# DoomBoxMk1.net
KiCad netlist of a schematic drawn in EAGLE
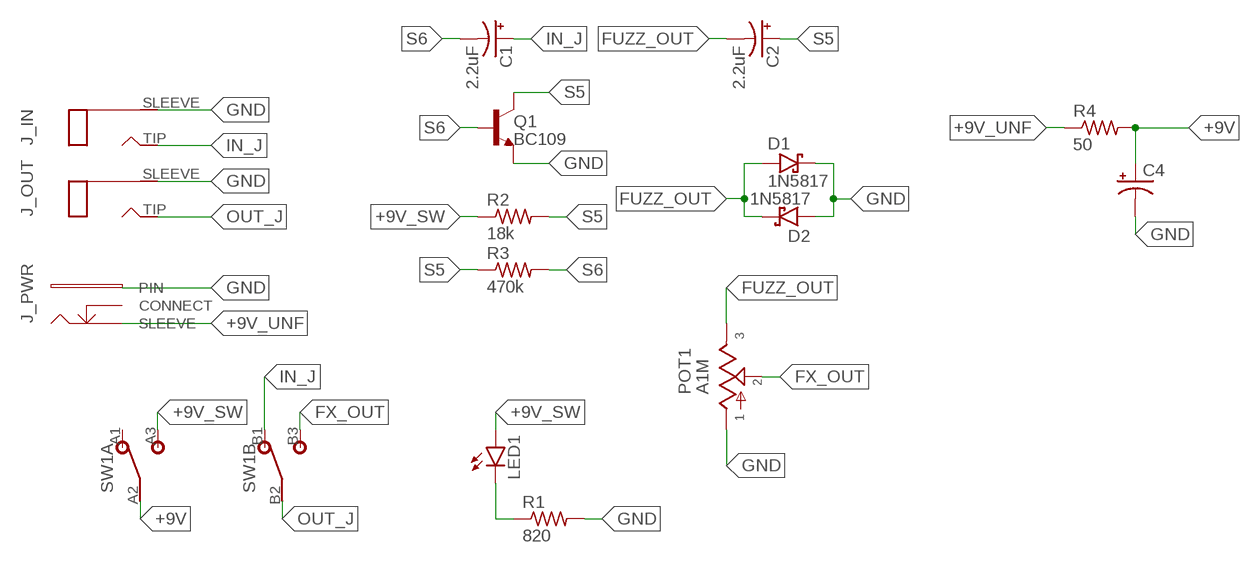
[diagram p0: schematic, sheet 1]

(export (version "E")
  (design (tool "Eeschema 10.0.6"))
  (components
    (comp (ref "C1")
      (value "2.2uF")
      (footprint "eagle-import:050_020_1")
      (libsource (lib "eagle-import") (part "0501"))
    )
    (comp (ref "C2")
      (value "2.2uF")
      (footprint "eagle-import:050_020_1")
      (libsource (lib "eagle-import") (part "0501"))
    )
    (comp (ref "C4")
      (value "0802")
      (footprint "eagle-import:080_035_2")
      (libsource (lib "eagle-import") (part "0802"))
    )
    (comp (ref "D1")
      (value "1N5817")
      (footprint "eagle-import:DO41-3")
      (libsource (lib "eagle-import") (part "1N5817"))
    )
    (comp (ref "D2")
      (value "1N5817")
      (footprint "eagle-import:DO41-3")
      (libsource (lib "eagle-import") (part "1N5817"))
    )
    (comp (ref "J_IN")
      (value "MONO")
      (footprint "eagle-import:MONO_JACK")
      (libsource (lib "eagle-import") (part "MONO"))
    )
    (comp (ref "J_OUT")
      (value "MONO")
      (footprint "eagle-import:MONO_JACK")
      (libsource (lib "eagle-import") (part "MONO"))
    )
    (comp (ref "J_PWR")
      (value "DC")
      (footprint "eagle-import:DC_POWER_JACK")
      (libsource (lib "eagle-import") (part "DC"))
    )
    (comp (ref "LED1")
      (value "LED5MM")
      (footprint "eagle-import:LED5MM")
      (libsource (lib "eagle-import") (part "LED5MM"))
    )
    (comp (ref "POT1")
      (value "A1M")
      (footprint "eagle-import:16MM-SQUARE")
      (libsource (lib "eagle-import") (part "POTS"))
    )
    (comp (ref "Q1")
      (value "BC109")
      (footprint "eagle-import:TO92-")
      (libsource (lib "eagle-import") (part "BC109"))
    )
    (comp (ref "R1")
      (value "820")
      (footprint "eagle-import:R0207_3")
      (libsource (lib "eagle-import") (part "6MM.3"))
    )
    (comp (ref "R2")
      (value "18k")
      (footprint "eagle-import:R0207_3")
      (libsource (lib "eagle-import") (part "6MM.3"))
    )
    (comp (ref "R3")
      (value "470k")
      (footprint "eagle-import:R0207_3")
      (libsource (lib "eagle-import") (part "6MM.3"))
    )
    (comp (ref "R4")
      (value "50")
      (footprint "eagle-import:R0207_3")
      (libsource (lib "eagle-import") (part "6MM.3"))
    )
    (comp (ref "SW1")
      (value "DPDT")
      (footprint "eagle-import:DPDT")
      (libsource (lib "eagle-import") (part "DPDT"))
    )
  )
  (nets
    (net (code "1") (name "+9V") (class "Default")
      (node (ref "C4") (pin "+") (pinfunction "+_+") (pintype "passive"))
      (node (ref "R4") (pin "2") (pinfunction "2_2") (pintype "passive"))
      (node (ref "SW1") (pin "A2") (pinfunction "2_A2") (pintype "passive"))
    )
    (net (code "2") (name "+9V_SW") (class "Default")
      (node (ref "LED1") (pin "A") (pinfunction "A_A") (pintype "passive"))
      (node (ref "R2") (pin "1") (pinfunction "1_1") (pintype "passive"))
      (node (ref "SW1") (pin "A3") (pinfunction "3_A3") (pintype "passive"))
    )
    (net (code "3") (name "+9V_UNF") (class "Default")
      (node (ref "J_PWR") (pin "SLEEVE") (pinfunction "SLEEVE_SLEEVE") (pintype "passive"))
      (node (ref "R4") (pin "1") (pinfunction "1_1") (pintype "passive"))
    )
    (net (code "4") (name "FUZZ_OUT") (class "Default")
      (node (ref "C2") (pin "-") (pinfunction "-_-") (pintype "passive"))
      (node (ref "D1") (pin "A") (pinfunction "A_A") (pintype "passive"))
      (node (ref "D2") (pin "C") (pinfunction "C_C") (pintype "passive"))
      (node (ref "POT1") (pin "3") (pinfunction "3_3") (pintype "passive"))
    )
    (net (code "5") (name "FX_OUT") (class "Default")
      (node (ref "POT1") (pin "2") (pinfunction "2_2") (pintype "passive"))
      (node (ref "SW1") (pin "B3") (pinfunction "3_B3") (pintype "passive"))
    )
    (net (code "6") (name "GND") (class "Default")
      (node (ref "C4") (pin "-") (pinfunction "-_-") (pintype "passive"))
      (node (ref "D1") (pin "C") (pinfunction "C_C") (pintype "passive"))
      (node (ref "D2") (pin "A") (pinfunction "A_A") (pintype "passive"))
      (node (ref "J_IN") (pin "SLEEVE") (pinfunction "SLEEVE_SLEEVE") (pintype "passive"))
      (node (ref "J_OUT") (pin "SLEEVE") (pinfunction "SLEEVE_SLEEVE") (pintype "passive"))
      (node (ref "J_PWR") (pin "PIN") (pinfunction "PIN_PIN") (pintype "passive"))
      (node (ref "POT1") (pin "1") (pinfunction "1_1") (pintype "passive"))
      (node (ref "Q1") (pin "1") (pinfunction "E_1") (pintype "passive"))
      (node (ref "R1") (pin "2") (pinfunction "2_2") (pintype "passive"))
    )
    (net (code "7") (name "IN_J") (class "Default")
      (node (ref "C1") (pin "+") (pinfunction "+_+") (pintype "passive"))
      (node (ref "J_IN") (pin "TIP") (pinfunction "TIP_TIP") (pintype "passive"))
      (node (ref "SW1") (pin "B1") (pinfunction "1_B1") (pintype "passive"))
    )
    (net (code "8") (name "Net-(LED1-C)") (class "Default")
      (node (ref "LED1") (pin "K") (pinfunction "C_K") (pintype "passive"))
      (node (ref "R1") (pin "1") (pinfunction "1_1") (pintype "passive"))
    )
    (net (code "9") (name "OUT_J") (class "Default")
      (node (ref "J_OUT") (pin "TIP") (pinfunction "TIP_TIP") (pintype "passive"))
      (node (ref "SW1") (pin "B2") (pinfunction "2_B2") (pintype "passive"))
    )
    (net (code "10") (name "S5") (class "Default")
      (node (ref "C2") (pin "+") (pinfunction "+_+") (pintype "passive"))
      (node (ref "Q1") (pin "3") (pinfunction "C_3") (pintype "passive"))
      (node (ref "R2") (pin "2") (pinfunction "2_2") (pintype "passive"))
      (node (ref "R3") (pin "1") (pinfunction "1_1") (pintype "passive"))
    )
    (net (code "11") (name "S6") (class "Default")
      (node (ref "C1") (pin "-") (pinfunction "-_-") (pintype "passive"))
      (node (ref "Q1") (pin "2") (pinfunction "B_2") (pintype "passive"))
      (node (ref "R3") (pin "2") (pinfunction "2_2") (pintype "passive"))
    )
    (net (code "12") (name "unconnected-(J_PWR-CONNECT-PadCLOSE)") (class "Default")
      (node (ref "J_PWR") (pin "CLOSE") (pinfunction "CONNECT_CLOSE") (pintype "passive"))
    )
    (net (code "13") (name "unconnected-(SW1A-1-PadA1)") (class "Default")
      (node (ref "SW1") (pin "A1") (pinfunction "1_A1") (pintype "passive"))
    )
  )
)
